# ETH_PART.net
KiCad netlist of a schematic drawn in Altium Designer
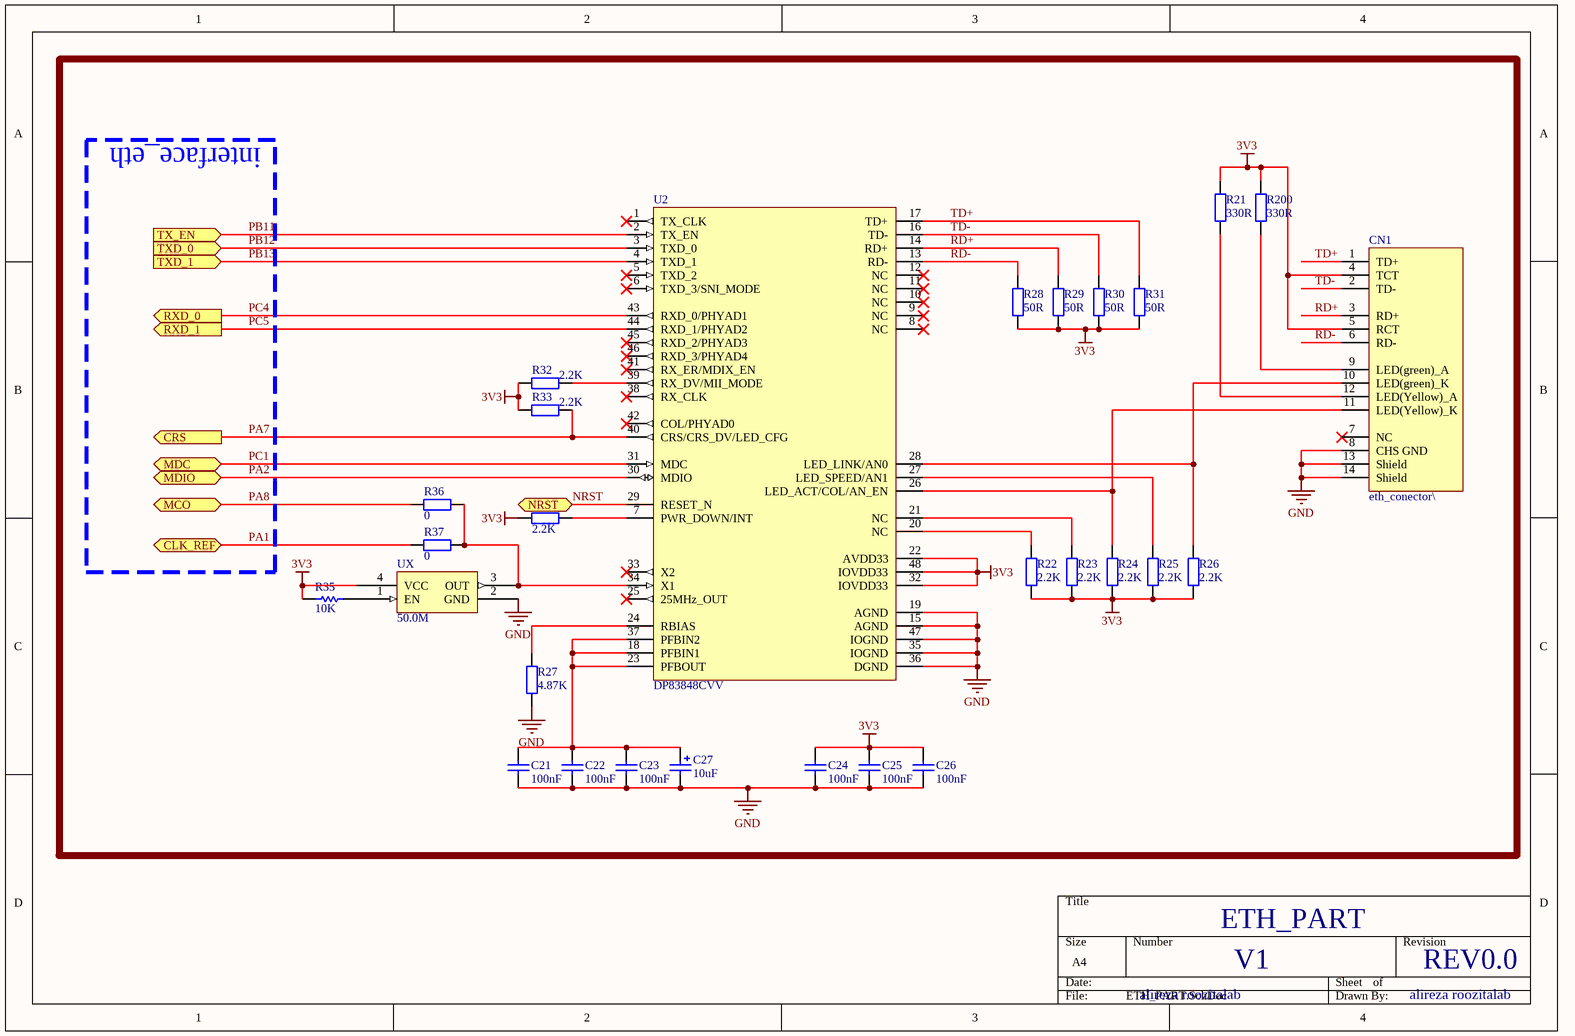
[diagram p0: ETH_PART.SchDoc]

(export (version "E")
  (design (tool "Eeschema 10.0.6"))
  (components
    (comp (ref "C21")
      (value "100nF")
      (footprint "0805.")
      (description "Capacitor")
      (fields (field (name "PUBLISHER") "Altium Limited"))
      (libsource (lib "STM32F407_144") (part "Cap"))
    )
    (comp (ref "C22")
      (value "100nF")
      (footprint "0805.")
      (description "Capacitor")
      (fields (field (name "PUBLISHER") "Altium Limited"))
      (libsource (lib "STM32F407_144") (part "Cap"))
    )
    (comp (ref "C23")
      (value "100nF")
      (footprint "0805.")
      (description "Capacitor")
      (fields (field (name "PUBLISHER") "Altium Limited"))
      (libsource (lib "STM32F407_144") (part "Cap"))
    )
    (comp (ref "C24")
      (value "100nF")
      (footprint "0805.")
      (description "Capacitor")
      (fields (field (name "PUBLISHER") "Altium Limited"))
      (libsource (lib "STM32F407_144") (part "Cap"))
    )
    (comp (ref "C25")
      (value "100nF")
      (footprint "0805.")
      (description "Capacitor")
      (fields (field (name "PUBLISHER") "Altium Limited"))
      (libsource (lib "STM32F407_144") (part "Cap"))
    )
    (comp (ref "C26")
      (value "100nF")
      (footprint "0805.")
      (description "Capacitor")
      (fields (field (name "PUBLISHER") "Altium Limited"))
      (libsource (lib "STM32F407_144") (part "Cap"))
    )
    (comp (ref "C27")
      (value "10uF")
      (footprint "C1206.")
      (description "Polarized Capacitor (Radial)")
      (fields (field (name "PUBLISHER") "Altium Limited"))
      (libsource (lib "STM32F407_144") (part "Cap Pol1"))
    )
    (comp (ref "CN1")
      (value "eth_conecto~{r}")
      (footprint "eth_conector")
      (libsource (lib "my dxp lib") (part "eth_conector{backslash}"))
    )
    (comp (ref "R21")
      (value "330R")
      (footprint "0805.")
      (description "Resistor")
      (fields (field (name "Comment") "Res2") (field (name "PUBLISHER") "Altium Limited"))
      (libsource (lib "") (part "Res2_1"))
    )
    (comp (ref "R22")
      (value "2.2K")
      (footprint "0805.")
      (description "Resistor")
      (fields (field (name "Comment") "Res2") (field (name "PUBLISHER") "Altium Limited"))
      (libsource (lib "") (part "Res2_1"))
    )
    (comp (ref "R23")
      (value "2.2K")
      (footprint "0805.")
      (description "Resistor")
      (fields (field (name "Comment") "Res2") (field (name "PUBLISHER") "Altium Limited"))
      (libsource (lib "") (part "Res2_1"))
    )
    (comp (ref "R24")
      (value "2.2K")
      (footprint "0805.")
      (description "Resistor")
      (fields (field (name "Comment") "Res2") (field (name "PUBLISHER") "Altium Limited"))
      (libsource (lib "") (part "Res2_1"))
    )
    (comp (ref "R25")
      (value "2.2K")
      (footprint "0805.")
      (description "Resistor")
      (fields (field (name "Comment") "Res2") (field (name "PUBLISHER") "Altium Limited"))
      (libsource (lib "") (part "Res2_1"))
    )
    (comp (ref "R26")
      (value "2.2K")
      (footprint "0805.")
      (description "Resistor")
      (fields (field (name "Comment") "Res2") (field (name "PUBLISHER") "Altium Limited"))
      (libsource (lib "") (part "Res2_1"))
    )
    (comp (ref "R27")
      (value "4.87K")
      (footprint "0805.")
      (description "Resistor")
      (fields (field (name "Comment") "Res2") (field (name "PUBLISHER") "Altium Limited"))
      (libsource (lib "") (part "Res2_1"))
    )
    (comp (ref "R28")
      (value "50R")
      (footprint "0805.")
      (description "Resistor")
      (fields (field (name "Comment") "Res2") (field (name "PUBLISHER") "Altium Limited"))
      (libsource (lib "") (part "Res2_1"))
    )
    (comp (ref "R29")
      (value "50R")
      (footprint "0805.")
      (description "Resistor")
      (fields (field (name "Comment") "Res2") (field (name "PUBLISHER") "Altium Limited"))
      (libsource (lib "") (part "Res2_1"))
    )
    (comp (ref "R30")
      (value "50R")
      (footprint "0805.")
      (description "Resistor")
      (fields (field (name "Comment") "Res2") (field (name "PUBLISHER") "Altium Limited"))
      (libsource (lib "") (part "Res2_1"))
    )
    (comp (ref "R31")
      (value "50R")
      (footprint "0805.")
      (description "Resistor")
      (fields (field (name "Comment") "Res2") (field (name "PUBLISHER") "Altium Limited"))
      (libsource (lib "") (part "Res2_1"))
    )
    (comp (ref "R32")
      (value "2.2K")
      (footprint "0805.")
      (description "Resistor")
      (fields (field (name "Comment") "Res2") (field (name "PUBLISHER") "Altium Limited"))
      (libsource (lib "STM32F407_144") (part "Res2"))
    )
    (comp (ref "R33")
      (value "2.2K")
      (footprint "0805.")
      (description "Resistor")
      (fields (field (name "Comment") "Res2") (field (name "PUBLISHER") "Altium Limited"))
      (libsource (lib "STM32F407_144") (part "Res2"))
    )
    (comp (ref "R34")
      (value "2.2K")
      (footprint "0805.")
      (description "Resistor")
      (fields (field (name "Comment") "Res2") (field (name "PUBLISHER") "Altium Limited"))
      (libsource (lib "STM32F407_144") (part "Res2"))
    )
    (comp (ref "R35")
      (value "10K")
      (footprint "0805.")
      (description "Resistor")
      (fields (field (name "PUBLISHER") "Altium Limited"))
      (libsource (lib "STM32F407_144") (part "Res1"))
    )
    (comp (ref "R36")
      (value "0")
      (footprint "0805.")
      (description "Resistor")
      (fields (field (name "Comment") "Res2") (field (name "PUBLISHER") "Altium Limited"))
      (libsource (lib "STM32F407_144") (part "Res2"))
    )
    (comp (ref "R37")
      (value "0")
      (footprint "0805.")
      (description "Resistor")
      (fields (field (name "Comment") "Res2") (field (name "PUBLISHER") "Altium Limited"))
      (libsource (lib "STM32F407_144") (part "Res2"))
    )
    (comp (ref "R200")
      (value "330R")
      (footprint "0805.")
      (description "Resistor")
      (fields (field (name "Comment") "Res2") (field (name "PUBLISHER") "Altium Limited"))
      (libsource (lib "") (part "Res2_1"))
    )
    (comp (ref "U2")
      (value "DP83848CVV")
      (footprint "LQFP48")
      (libsource (lib "STM32F407_144") (part "DP83848CVV"))
    )
    (comp (ref "UX")
      (value "50.0M")
      (footprint "oscillator_50MHZ")
      (libsource (lib "STM32F407_144") (part "SM7745HEV-50.0M"))
    )
  )
  (nets
    (net (code "1") (name "/NRST") (class "Default")
      (node (ref "U2") (pin "29") (pinfunction "RESET_N_29") (pintype "passive"))
    )
    (net (code "2") (name "/PA1") (class "Default")
      (node (ref "R37") (pin "1") (pinfunction "1_1") (pintype "passive"))
    )
    (net (code "3") (name "/PA2") (class "Default")
      (node (ref "U2") (pin "30") (pinfunction "MDIO_30") (pintype "bidirectional"))
    )
    (net (code "4") (name "/PA7") (class "Default")
      (node (ref "R33") (pin "2") (pinfunction "2_2") (pintype "passive"))
      (node (ref "U2") (pin "40") (pinfunction "CRS/CRS_DV/LED_CFG_40") (pintype "output"))
    )
    (net (code "5") (name "/PA8") (class "Default")
      (node (ref "R36") (pin "1") (pinfunction "1_1") (pintype "passive"))
    )
    (net (code "6") (name "/PB11") (class "Default")
      (node (ref "U2") (pin "2") (pinfunction "TX_EN_2") (pintype "input"))
    )
    (net (code "7") (name "/PB12") (class "Default")
      (node (ref "U2") (pin "3") (pinfunction "TXD_0_3") (pintype "input"))
    )
    (net (code "8") (name "/PB13") (class "Default")
      (node (ref "U2") (pin "4") (pinfunction "TXD_1_4") (pintype "input"))
    )
    (net (code "9") (name "/PC1") (class "Default")
      (node (ref "U2") (pin "31") (pinfunction "MDC_31") (pintype "input"))
    )
    (net (code "10") (name "/PC4") (class "Default")
      (node (ref "U2") (pin "43") (pinfunction "RXD_0/PHYAD1_43") (pintype "output"))
    )
    (net (code "11") (name "/PC5") (class "Default")
      (node (ref "U2") (pin "44") (pinfunction "RXD_1/PHYAD2_44") (pintype "output"))
    )
    (net (code "12") (name "/RD+") (class "Default")
      (node (ref "CN1") (pin "3") (pinfunction "RD+_3") (pintype "passive"))
      (node (ref "R29") (pin "2") (pinfunction "2_2") (pintype "passive"))
      (node (ref "U2") (pin "14") (pinfunction "RD+_14") (pintype "passive"))
    )
    (net (code "13") (name "/RD-") (class "Default")
      (node (ref "CN1") (pin "6") (pinfunction "RD-_6") (pintype "passive"))
      (node (ref "R28") (pin "2") (pinfunction "2_2") (pintype "passive"))
      (node (ref "U2") (pin "13") (pinfunction "RD-_13") (pintype "passive"))
    )
    (net (code "14") (name "/TD+") (class "Default")
      (node (ref "CN1") (pin "1") (pinfunction "TD+_1") (pintype "passive"))
      (node (ref "R31") (pin "2") (pinfunction "2_2") (pintype "passive"))
      (node (ref "U2") (pin "17") (pinfunction "TD+_17") (pintype "passive"))
    )
    (net (code "15") (name "/TD-") (class "Default")
      (node (ref "CN1") (pin "2") (pinfunction "TD-_2") (pintype "passive"))
      (node (ref "R30") (pin "2") (pinfunction "2_2") (pintype "passive"))
      (node (ref "U2") (pin "16") (pinfunction "TD-_16") (pintype "passive"))
    )
    (net (code "16") (name "3V3") (class "Default")
      (node (ref "C24") (pin "1") (pinfunction "1_1") (pintype "passive"))
      (node (ref "C25") (pin "1") (pinfunction "1_1") (pintype "passive"))
      (node (ref "C26") (pin "1") (pinfunction "1_1") (pintype "passive"))
      (node (ref "CN1") (pin "4") (pinfunction "TCT_4") (pintype "passive"))
      (node (ref "CN1") (pin "5") (pinfunction "RCT_5") (pintype "passive"))
      (node (ref "R200") (pin "2") (pinfunction "2_2") (pintype "passive"))
      (node (ref "R21") (pin "2") (pinfunction "2_2") (pintype "passive"))
      (node (ref "R22") (pin "1") (pinfunction "1_1") (pintype "passive"))
      (node (ref "R23") (pin "1") (pinfunction "1_1") (pintype "passive"))
      (node (ref "R24") (pin "1") (pinfunction "1_1") (pintype "passive"))
      (node (ref "R25") (pin "1") (pinfunction "1_1") (pintype "passive"))
      (node (ref "R26") (pin "1") (pinfunction "1_1") (pintype "passive"))
      (node (ref "R28") (pin "1") (pinfunction "1_1") (pintype "passive"))
      (node (ref "R29") (pin "1") (pinfunction "1_1") (pintype "passive"))
      (node (ref "R30") (pin "1") (pinfunction "1_1") (pintype "passive"))
      (node (ref "R31") (pin "1") (pinfunction "1_1") (pintype "passive"))
      (node (ref "R32") (pin "1") (pinfunction "1_1") (pintype "passive"))
      (node (ref "R33") (pin "1") (pinfunction "1_1") (pintype "passive"))
      (node (ref "R34") (pin "1") (pinfunction "1_1") (pintype "passive"))
      (node (ref "R35") (pin "1") (pinfunction "1_1") (pintype "passive"))
      (node (ref "U2") (pin "22") (pinfunction "AVDD33_22") (pintype "passive"))
      (node (ref "U2") (pin "32") (pinfunction "IOVDD33_32") (pintype "passive"))
      (node (ref "U2") (pin "48") (pinfunction "IOVDD33_48") (pintype "passive"))
      (node (ref "UX") (pin "4") (pinfunction "VCC_4") (pintype "passive"))
    )
    (net (code "17") (name "GND") (class "Default")
      (node (ref "C21") (pin "2") (pinfunction "2_2") (pintype "passive"))
      (node (ref "C22") (pin "2") (pinfunction "2_2") (pintype "passive"))
      (node (ref "C23") (pin "2") (pinfunction "2_2") (pintype "passive"))
      (node (ref "C24") (pin "2") (pinfunction "2_2") (pintype "passive"))
      (node (ref "C25") (pin "2") (pinfunction "2_2") (pintype "passive"))
      (node (ref "C26") (pin "2") (pinfunction "2_2") (pintype "passive"))
      (node (ref "C27") (pin "2") (pinfunction "2_2") (pintype "passive"))
      (node (ref "CN1") (pin "13") (pinfunction "Shield_13") (pintype "passive"))
      (node (ref "CN1") (pin "14") (pinfunction "Shield_14") (pintype "passive"))
      (node (ref "CN1") (pin "8") (pinfunction "CHS_GND_8") (pintype "passive"))
      (node (ref "R27") (pin "1") (pinfunction "1_1") (pintype "passive"))
      (node (ref "U2") (pin "15") (pinfunction "AGND_15") (pintype "passive"))
      (node (ref "U2") (pin "19") (pinfunction "AGND_19") (pintype "passive"))
      (node (ref "U2") (pin "35") (pinfunction "IOGND_35") (pintype "passive"))
      (node (ref "U2") (pin "36") (pinfunction "DGND_36") (pintype "passive"))
      (node (ref "U2") (pin "47") (pinfunction "IOGND_47") (pintype "passive"))
      (node (ref "UX") (pin "2") (pinfunction "GND_2") (pintype "passive"))
    )
    (net (code "18") (name "Net-(CN1-LED(Yellow)_A)") (class "Default")
      (node (ref "CN1") (pin "12") (pinfunction "LED(Yellow)_A_12") (pintype "passive"))
      (node (ref "R21") (pin "1") (pinfunction "1_1") (pintype "passive"))
    )
    (net (code "19") (name "Net-(CN1-LED(Yellow)_K)") (class "Default")
      (node (ref "CN1") (pin "11") (pinfunction "LED(Yellow)_K_11") (pintype "passive"))
      (node (ref "R24") (pin "2") (pinfunction "2_2") (pintype "passive"))
      (node (ref "U2") (pin "26") (pinfunction "LED_ACT/COL/AN_EN_26") (pintype "passive"))
    )
    (net (code "20") (name "Net-(CN1-LED(green)_A)") (class "Default")
      (node (ref "CN1") (pin "9") (pinfunction "LED(green)_A_9") (pintype "passive"))
      (node (ref "R200") (pin "1") (pinfunction "1_1") (pintype "passive"))
    )
    (net (code "21") (name "Net-(CN1-LED(green)_K)") (class "Default")
      (node (ref "CN1") (pin "10") (pinfunction "LED(green)_K_10") (pintype "passive"))
      (node (ref "R26") (pin "2") (pinfunction "2_2") (pintype "passive"))
      (node (ref "U2") (pin "28") (pinfunction "LED_LINK/AN0_28") (pintype "passive"))
    )
    (net (code "22") (name "Net-(R22-Pad2)") (class "Default")
      (node (ref "R22") (pin "2") (pinfunction "2_2") (pintype "passive"))
      (node (ref "U2") (pin "20") (pinfunction "NC_20") (pintype "passive"))
    )
    (net (code "23") (name "Net-(R23-Pad2)") (class "Default")
      (node (ref "R23") (pin "2") (pinfunction "2_2") (pintype "passive"))
      (node (ref "U2") (pin "21") (pinfunction "NC_21") (pintype "passive"))
    )
    (net (code "24") (name "Net-(U2-LED_SPEED{slash}AN1)") (class "Default")
      (node (ref "R25") (pin "2") (pinfunction "2_2") (pintype "passive"))
      (node (ref "U2") (pin "27") (pinfunction "LED_SPEED/AN1_27") (pintype "passive"))
    )
    (net (code "25") (name "Net-(U2-PFBIN1)") (class "Default")
      (node (ref "C21") (pin "1") (pinfunction "1_1") (pintype "passive"))
      (node (ref "C22") (pin "1") (pinfunction "1_1") (pintype "passive"))
      (node (ref "C23") (pin "1") (pinfunction "1_1") (pintype "passive"))
      (node (ref "C27") (pin "1") (pinfunction "1_1") (pintype "passive"))
      (node (ref "U2") (pin "18") (pinfunction "PFBIN1_18") (pintype "passive"))
      (node (ref "U2") (pin "23") (pinfunction "PFBOUT_23") (pintype "passive"))
      (node (ref "U2") (pin "37") (pinfunction "PFBIN2_37") (pintype "passive"))
    )
    (net (code "26") (name "Net-(U2-PWR_DOWN{slash}INT)") (class "Default")
      (node (ref "R34") (pin "2") (pinfunction "2_2") (pintype "passive"))
      (node (ref "U2") (pin "7") (pinfunction "PWR_DOWN/INT_7") (pintype "passive"))
    )
    (net (code "27") (name "Net-(U2-RBIAS)") (class "Default")
      (node (ref "R27") (pin "2") (pinfunction "2_2") (pintype "passive"))
      (node (ref "U2") (pin "24") (pinfunction "RBIAS_24") (pintype "passive"))
    )
    (net (code "28") (name "Net-(U2-RX_DV{slash}MII_MODE)") (class "Default")
      (node (ref "R32") (pin "2") (pinfunction "2_2") (pintype "passive"))
      (node (ref "U2") (pin "39") (pinfunction "RX_DV/MII_MODE_39") (pintype "output"))
    )
    (net (code "29") (name "Net-(U2-X1)") (class "Default")
      (node (ref "R36") (pin "2") (pinfunction "2_2") (pintype "passive"))
      (node (ref "R37") (pin "2") (pinfunction "2_2") (pintype "passive"))
      (node (ref "U2") (pin "34") (pinfunction "X1_34") (pintype "input"))
      (node (ref "UX") (pin "3") (pinfunction "OUT_3") (pintype "output"))
    )
    (net (code "30") (name "Net-(UX-EN)") (class "Default")
      (node (ref "R35") (pin "2") (pinfunction "2_2") (pintype "passive"))
      (node (ref "UX") (pin "1") (pinfunction "EN_1") (pintype "input"))
    )
    (net (code "31") (name "unconnected-(CN1-NC-Pad7)") (class "Default")
      (node (ref "CN1") (pin "7") (pinfunction "NC_7") (pintype "passive+no_connect"))
    )
    (net (code "32") (name "unconnected-(U2-25MHz_OUT-Pad25)") (class "Default")
      (node (ref "U2") (pin "25") (pinfunction "25MHz_OUT_25") (pintype "output+no_connect"))
    )
    (net (code "33") (name "unconnected-(U2-COL{slash}PHYAD0-Pad42)") (class "Default")
      (node (ref "U2") (pin "42") (pinfunction "COL/PHYAD0_42") (pintype "output+no_connect"))
    )
    (net (code "34") (name "unconnected-(U2-NC-Pad8)") (class "Default")
      (node (ref "U2") (pin "8") (pinfunction "NC_8") (pintype "passive+no_connect"))
    )
    (net (code "35") (name "unconnected-(U2-NC-Pad9)") (class "Default")
      (node (ref "U2") (pin "9") (pinfunction "NC_9") (pintype "passive+no_connect"))
    )
    (net (code "36") (name "unconnected-(U2-NC-Pad10)") (class "Default")
      (node (ref "U2") (pin "10") (pinfunction "NC_10") (pintype "passive+no_connect"))
    )
    (net (code "37") (name "unconnected-(U2-NC-Pad11)") (class "Default")
      (node (ref "U2") (pin "11") (pinfunction "NC_11") (pintype "passive+no_connect"))
    )
    (net (code "38") (name "unconnected-(U2-NC-Pad12)") (class "Default")
      (node (ref "U2") (pin "12") (pinfunction "NC_12") (pintype "passive+no_connect"))
    )
    (net (code "39") (name "unconnected-(U2-RXD_2{slash}PHYAD3-Pad45)") (class "Default")
      (node (ref "U2") (pin "45") (pinfunction "RXD_2/PHYAD3_45") (pintype "output+no_connect"))
    )
    (net (code "40") (name "unconnected-(U2-RXD_3{slash}PHYAD4-Pad46)") (class "Default")
      (node (ref "U2") (pin "46") (pinfunction "RXD_3/PHYAD4_46") (pintype "output+no_connect"))
    )
    (net (code "41") (name "unconnected-(U2-RX_CLK-Pad38)") (class "Default")
      (node (ref "U2") (pin "38") (pinfunction "RX_CLK_38") (pintype "output+no_connect"))
    )
    (net (code "42") (name "unconnected-(U2-RX_ER{slash}MDIX_EN-Pad41)") (class "Default")
      (node (ref "U2") (pin "41") (pinfunction "RX_ER/MDIX_EN_41") (pintype "output+no_connect"))
    )
    (net (code "43") (name "unconnected-(U2-TXD_2-Pad5)") (class "Default")
      (node (ref "U2") (pin "5") (pinfunction "TXD_2_5") (pintype "input+no_connect"))
    )
    (net (code "44") (name "unconnected-(U2-TXD_3{slash}SNI_MODE-Pad6)") (class "Default")
      (node (ref "U2") (pin "6") (pinfunction "TXD_3/SNI_MODE_6") (pintype "input+no_connect"))
    )
    (net (code "45") (name "unconnected-(U2-TX_CLK-Pad1)") (class "Default")
      (node (ref "U2") (pin "1") (pinfunction "TX_CLK_1") (pintype "output+no_connect"))
    )
    (net (code "46") (name "unconnected-(U2-X2-Pad33)") (class "Default")
      (node (ref "U2") (pin "33") (pinfunction "X2_33") (pintype "output+no_connect"))
    )
  )
)
